# Board_AB_Thumb.net
KiCad netlist of a schematic drawn in Altium Designer
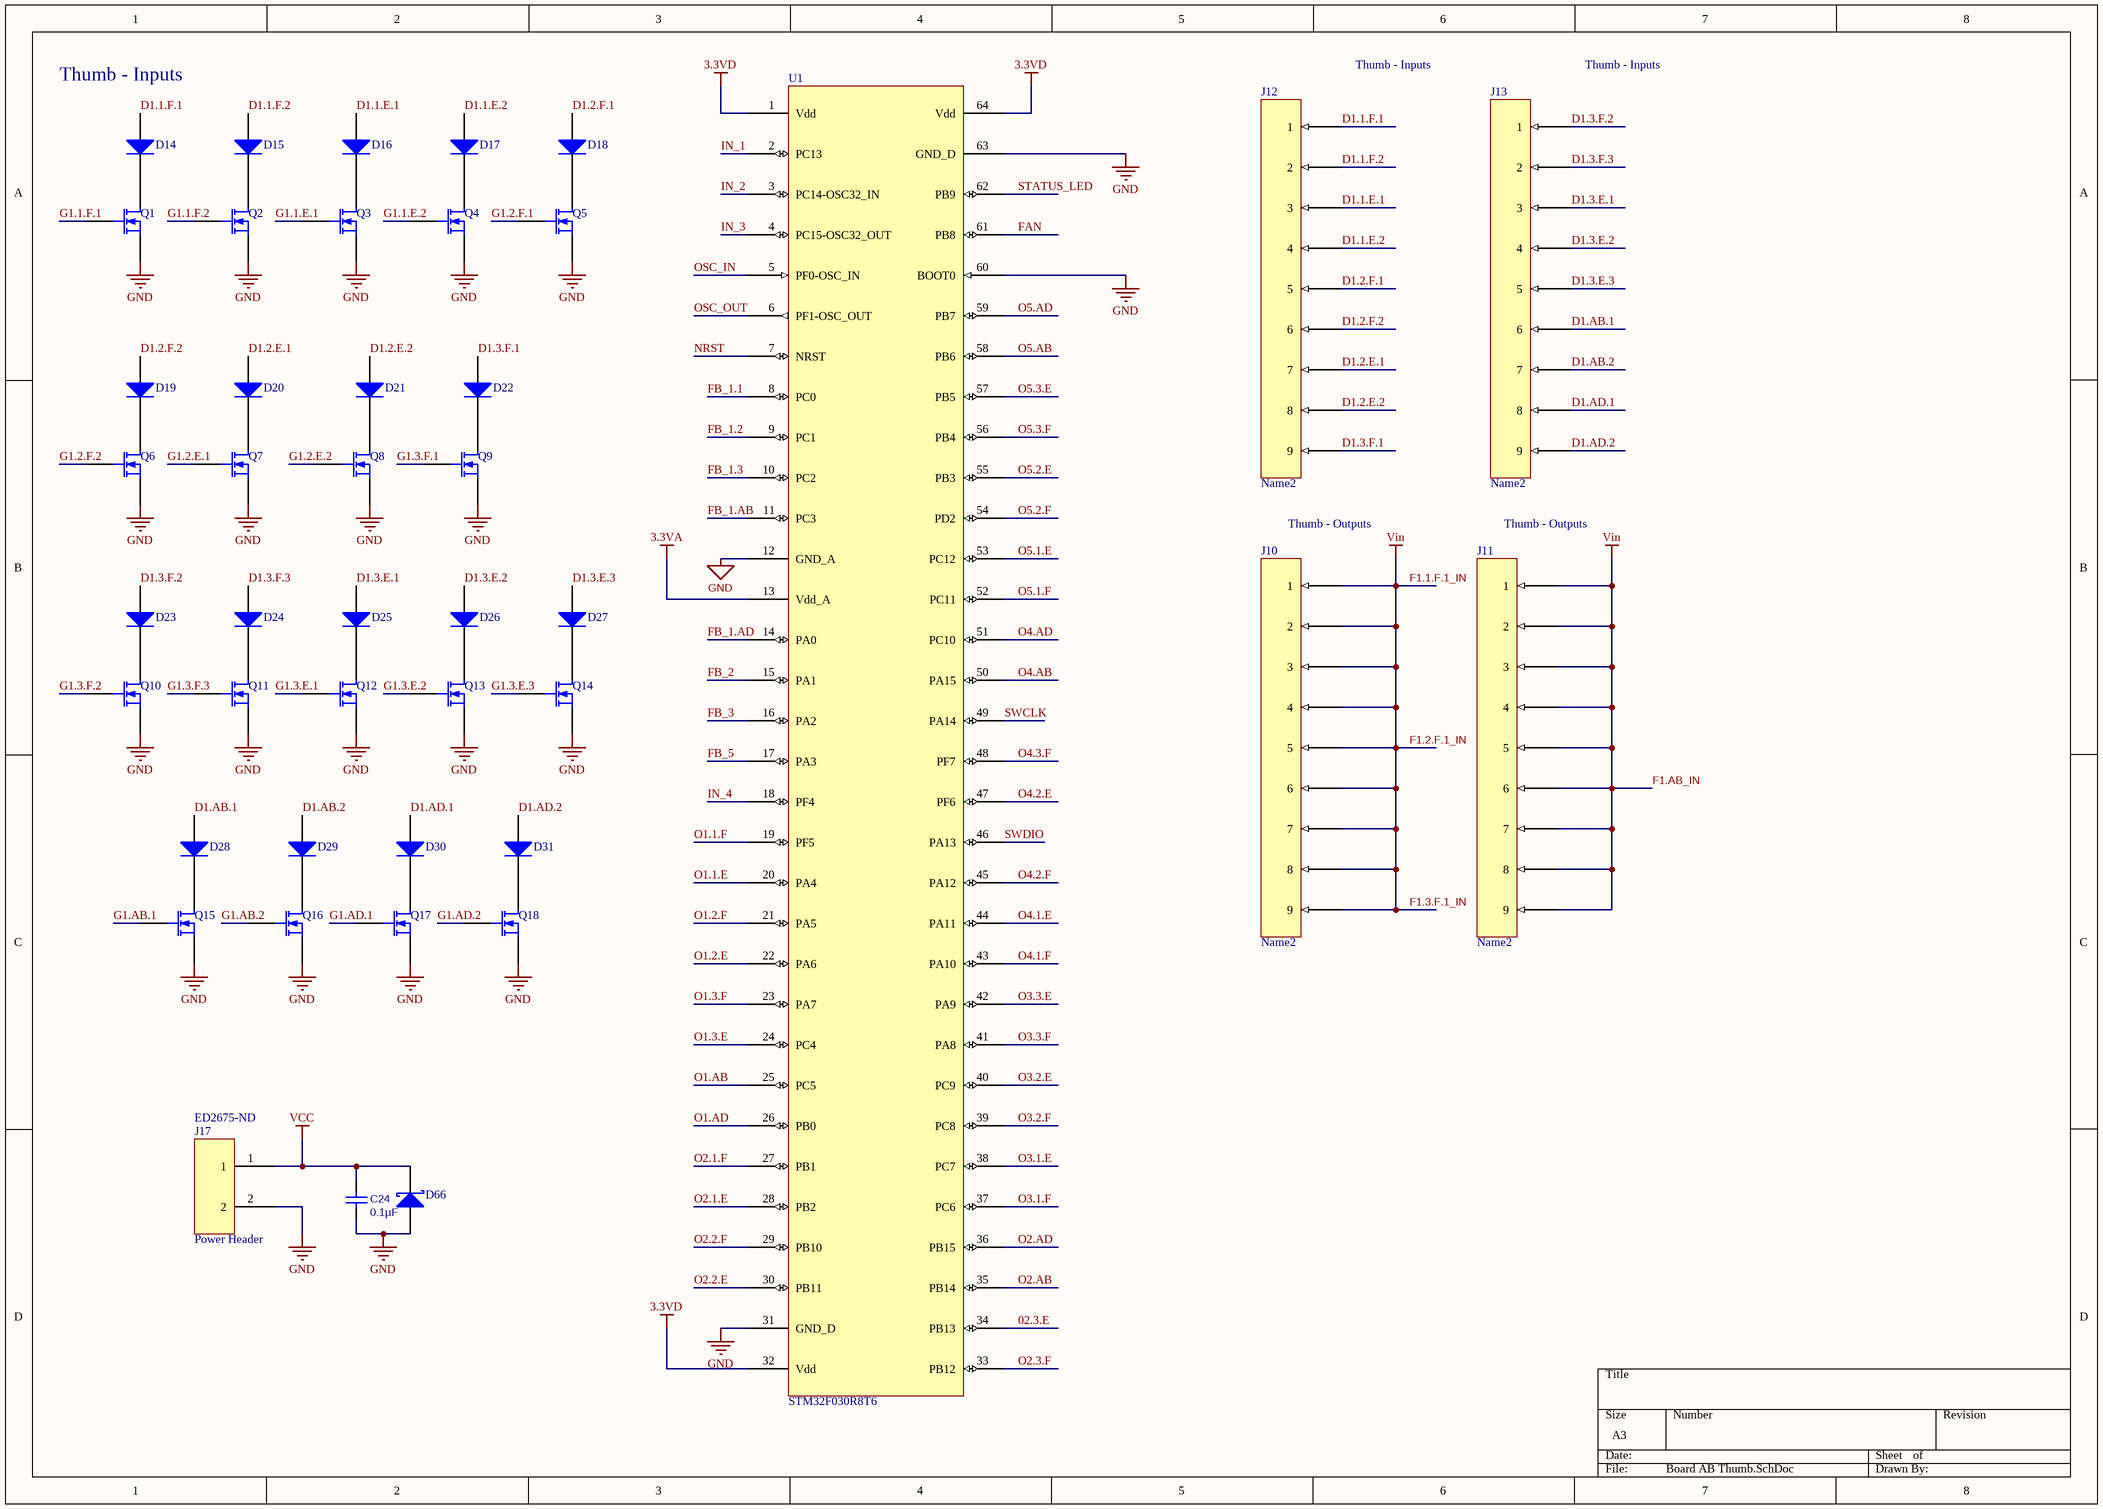
[diagram p0: Board AB Thumb.SchDoc]

(export (version "E")
  (design (tool "Eeschema 10.0.6"))
  (components
    (comp (ref "C24")
      (value "0.1µF")
      (footprint "TDK C-Series (1608)")
      (description "Capacitor")
      (fields (field (name "PUBLISHER") "Altium Limited"))
      (libsource (lib "Miscellaneous Devices") (part "Cap"))
    )
    (comp (ref "D14")
      (value "de")
      (footprint "SMC")
      (description "Default Diode")
      (fields (field (name "PUBLISHER") "Altium Limited"))
      (libsource (lib "Miscellaneous Devices") (part "Diode"))
    )
    (comp (ref "D15")
      (value "de")
      (footprint "SMC")
      (description "Default Diode")
      (fields (field (name "PUBLISHER") "Altium Limited"))
      (libsource (lib "Miscellaneous Devices") (part "Diode"))
    )
    (comp (ref "D16")
      (value "de")
      (footprint "SMC")
      (description "Default Diode")
      (fields (field (name "PUBLISHER") "Altium Limited"))
      (libsource (lib "Miscellaneous Devices") (part "Diode"))
    )
    (comp (ref "D17")
      (value "de")
      (footprint "SMC")
      (description "Default Diode")
      (fields (field (name "PUBLISHER") "Altium Limited"))
      (libsource (lib "Miscellaneous Devices") (part "Diode"))
    )
    (comp (ref "D18")
      (value "de")
      (footprint "SMC")
      (description "Default Diode")
      (fields (field (name "PUBLISHER") "Altium Limited"))
      (libsource (lib "Miscellaneous Devices") (part "Diode"))
    )
    (comp (ref "D19")
      (value "de")
      (footprint "SMC")
      (description "Default Diode")
      (fields (field (name "PUBLISHER") "Altium Limited"))
      (libsource (lib "Miscellaneous Devices") (part "Diode"))
    )
    (comp (ref "D20")
      (value "de")
      (footprint "SMC")
      (description "Default Diode")
      (fields (field (name "PUBLISHER") "Altium Limited"))
      (libsource (lib "Miscellaneous Devices") (part "Diode"))
    )
    (comp (ref "D21")
      (value "de")
      (footprint "SMC")
      (description "Default Diode")
      (fields (field (name "PUBLISHER") "Altium Limited"))
      (libsource (lib "Miscellaneous Devices") (part "Diode"))
    )
    (comp (ref "D22")
      (value "de")
      (footprint "SMC")
      (description "Default Diode")
      (fields (field (name "PUBLISHER") "Altium Limited"))
      (libsource (lib "Miscellaneous Devices") (part "Diode"))
    )
    (comp (ref "D23")
      (value "de")
      (footprint "SMC")
      (description "Default Diode")
      (fields (field (name "PUBLISHER") "Altium Limited"))
      (libsource (lib "Miscellaneous Devices") (part "Diode"))
    )
    (comp (ref "D24")
      (value "de")
      (footprint "SMC")
      (description "Default Diode")
      (fields (field (name "PUBLISHER") "Altium Limited"))
      (libsource (lib "Miscellaneous Devices") (part "Diode"))
    )
    (comp (ref "D25")
      (value "de")
      (footprint "SMC")
      (description "Default Diode")
      (fields (field (name "PUBLISHER") "Altium Limited"))
      (libsource (lib "Miscellaneous Devices") (part "Diode"))
    )
    (comp (ref "D26")
      (value "de")
      (footprint "SMC")
      (description "Default Diode")
      (fields (field (name "PUBLISHER") "Altium Limited"))
      (libsource (lib "Miscellaneous Devices") (part "Diode"))
    )
    (comp (ref "D27")
      (value "de")
      (footprint "SMC")
      (description "Default Diode")
      (fields (field (name "PUBLISHER") "Altium Limited"))
      (libsource (lib "Miscellaneous Devices") (part "Diode"))
    )
    (comp (ref "D28")
      (value "de")
      (footprint "SMC")
      (description "Default Diode")
      (fields (field (name "PUBLISHER") "Altium Limited"))
      (libsource (lib "Miscellaneous Devices") (part "Diode"))
    )
    (comp (ref "D29")
      (value "de")
      (footprint "SMC")
      (description "Default Diode")
      (fields (field (name "PUBLISHER") "Altium Limited"))
      (libsource (lib "Miscellaneous Devices") (part "Diode"))
    )
    (comp (ref "D30")
      (value "de")
      (footprint "SMC")
      (description "Default Diode")
      (fields (field (name "PUBLISHER") "Altium Limited"))
      (libsource (lib "Miscellaneous Devices") (part "Diode"))
    )
    (comp (ref "D31")
      (value "de")
      (footprint "SMC")
      (description "Default Diode")
      (fields (field (name "PUBLISHER") "Altium Limited"))
      (libsource (lib "Miscellaneous Devices") (part "Diode"))
    )
    (comp (ref "D66")
      (value "Diode BAT17")
      (footprint "SOT-23_N")
      (description "Silicon RF Schottky Diode for Mixer Applications in the VHF/UHF Range")
      (fields (field (name "PUBLISHER") "Altium Limited"))
      (libsource (lib "Miscellaneous Devices") (part "Diode BAT17"))
    )
    (comp (ref "J10")
      (value "Name2")
      (description "9 Position header")
      (libsource (lib "Schematics Library") (part "Name2"))
    )
    (comp (ref "J11")
      (value "Name2")
      (description "9 Position header")
      (libsource (lib "Schematics Library") (part "Name2"))
    )
    (comp (ref "J12")
      (value "Name2")
      (description "9 Position header")
      (libsource (lib "Schematics Library") (part "Name2"))
    )
    (comp (ref "J13")
      (value "Name2")
      (description "9 Position header")
      (libsource (lib "Schematics Library") (part "Name2"))
    )
    (comp (ref "J17")
      (value "Power Header")
      (fields (field (name "SUPPLIER PART NUMBER 1") "ED2675-ND"))
      (libsource (lib "Schematics Library") (part "Power Header"))
    )
    (comp (ref "Q1")
      (value "~")
      (description "N-Channel MOSFET")
      (fields (field (name "PUBLISHER") "Altium Limited"))
      (libsource (lib "Miscellaneous Devices") (part "MOSFET-N"))
    )
    (comp (ref "Q2")
      (value "~")
      (description "N-Channel MOSFET")
      (fields (field (name "PUBLISHER") "Altium Limited"))
      (libsource (lib "Miscellaneous Devices") (part "MOSFET-N"))
    )
    (comp (ref "Q3")
      (value "~")
      (description "N-Channel MOSFET")
      (fields (field (name "PUBLISHER") "Altium Limited"))
      (libsource (lib "Miscellaneous Devices") (part "MOSFET-N"))
    )
    (comp (ref "Q4")
      (value "~")
      (description "N-Channel MOSFET")
      (fields (field (name "PUBLISHER") "Altium Limited"))
      (libsource (lib "Miscellaneous Devices") (part "MOSFET-N"))
    )
    (comp (ref "Q5")
      (value "~")
      (description "N-Channel MOSFET")
      (fields (field (name "PUBLISHER") "Altium Limited"))
      (libsource (lib "Miscellaneous Devices") (part "MOSFET-N"))
    )
    (comp (ref "Q6")
      (value "~")
      (description "N-Channel MOSFET")
      (fields (field (name "PUBLISHER") "Altium Limited"))
      (libsource (lib "Miscellaneous Devices") (part "MOSFET-N"))
    )
    (comp (ref "Q7")
      (value "~")
      (description "N-Channel MOSFET")
      (fields (field (name "PUBLISHER") "Altium Limited"))
      (libsource (lib "Miscellaneous Devices") (part "MOSFET-N"))
    )
    (comp (ref "Q8")
      (value "~")
      (description "N-Channel MOSFET")
      (fields (field (name "PUBLISHER") "Altium Limited"))
      (libsource (lib "Miscellaneous Devices") (part "MOSFET-N"))
    )
    (comp (ref "Q9")
      (value "~")
      (description "N-Channel MOSFET")
      (fields (field (name "PUBLISHER") "Altium Limited"))
      (libsource (lib "Miscellaneous Devices") (part "MOSFET-N"))
    )
    (comp (ref "Q10")
      (value "~")
      (description "N-Channel MOSFET")
      (fields (field (name "PUBLISHER") "Altium Limited"))
      (libsource (lib "Miscellaneous Devices") (part "MOSFET-N"))
    )
    (comp (ref "Q11")
      (value "~")
      (description "N-Channel MOSFET")
      (fields (field (name "PUBLISHER") "Altium Limited"))
      (libsource (lib "Miscellaneous Devices") (part "MOSFET-N"))
    )
    (comp (ref "Q12")
      (value "~")
      (description "N-Channel MOSFET")
      (fields (field (name "PUBLISHER") "Altium Limited"))
      (libsource (lib "Miscellaneous Devices") (part "MOSFET-N"))
    )
    (comp (ref "Q13")
      (value "~")
      (description "N-Channel MOSFET")
      (fields (field (name "PUBLISHER") "Altium Limited"))
      (libsource (lib "Miscellaneous Devices") (part "MOSFET-N"))
    )
    (comp (ref "Q14")
      (value "~")
      (description "N-Channel MOSFET")
      (fields (field (name "PUBLISHER") "Altium Limited"))
      (libsource (lib "Miscellaneous Devices") (part "MOSFET-N"))
    )
    (comp (ref "Q15")
      (value "~")
      (description "N-Channel MOSFET")
      (fields (field (name "PUBLISHER") "Altium Limited"))
      (libsource (lib "Miscellaneous Devices") (part "MOSFET-N"))
    )
    (comp (ref "Q16")
      (value "~")
      (description "N-Channel MOSFET")
      (fields (field (name "PUBLISHER") "Altium Limited"))
      (libsource (lib "Miscellaneous Devices") (part "MOSFET-N"))
    )
    (comp (ref "Q17")
      (value "~")
      (description "N-Channel MOSFET")
      (fields (field (name "PUBLISHER") "Altium Limited"))
      (libsource (lib "Miscellaneous Devices") (part "MOSFET-N"))
    )
    (comp (ref "Q18")
      (value "~")
      (description "N-Channel MOSFET")
      (fields (field (name "PUBLISHER") "Altium Limited"))
      (libsource (lib "Miscellaneous Devices") (part "MOSFET-N"))
    )
    (comp (ref "U1") (value "STM32F030R8T6") (libsource (lib "Schematics Library") (part "STM32F030R8T6")))
  )
  (nets
    (net (code "1") (name "/02.3.E") (class "Default")
      (node (ref "U1") (pin "34") (pinfunction "PB13_34") (pintype "bidirectional"))
    )
    (net (code "2") (name "/D1.1.E.1") (class "Default")
      (node (ref "D16") (pin "1") (pinfunction "A_1") (pintype "passive"))
      (node (ref "J12") (pin "3") (pinfunction "3_3") (pintype "input"))
    )
    (net (code "3") (name "/D1.1.E.2") (class "Default")
      (node (ref "D17") (pin "1") (pinfunction "A_1") (pintype "passive"))
      (node (ref "J12") (pin "4") (pinfunction "4_4") (pintype "input"))
    )
    (net (code "4") (name "/D1.1.F.1") (class "Default")
      (node (ref "D14") (pin "1") (pinfunction "A_1") (pintype "passive"))
      (node (ref "J12") (pin "1") (pinfunction "1_1") (pintype "input"))
    )
    (net (code "5") (name "/D1.1.F.2") (class "Default")
      (node (ref "D15") (pin "1") (pinfunction "A_1") (pintype "passive"))
      (node (ref "J12") (pin "66") (pinfunction "2_66") (pintype "input"))
    )
    (net (code "6") (name "/D1.2.E.1") (class "Default")
      (node (ref "D20") (pin "1") (pinfunction "A_1") (pintype "passive"))
      (node (ref "J12") (pin "7") (pinfunction "7_7") (pintype "input"))
    )
    (net (code "7") (name "/D1.2.E.2") (class "Default")
      (node (ref "D21") (pin "1") (pinfunction "A_1") (pintype "passive"))
      (node (ref "J12") (pin "8") (pinfunction "8_8") (pintype "input"))
    )
    (net (code "8") (name "/D1.2.F.1") (class "Default")
      (node (ref "D18") (pin "1") (pinfunction "A_1") (pintype "passive"))
      (node (ref "J12") (pin "5") (pinfunction "5_5") (pintype "input"))
    )
    (net (code "9") (name "/D1.2.F.2") (class "Default")
      (node (ref "D19") (pin "1") (pinfunction "A_1") (pintype "passive"))
      (node (ref "J12") (pin "6") (pinfunction "6_6") (pintype "input"))
    )
    (net (code "10") (name "/D1.3.E.1") (class "Default")
      (node (ref "D25") (pin "1") (pinfunction "A_1") (pintype "passive"))
      (node (ref "J13") (pin "3") (pinfunction "3_3") (pintype "input"))
    )
    (net (code "11") (name "/D1.3.E.2") (class "Default")
      (node (ref "D26") (pin "1") (pinfunction "A_1") (pintype "passive"))
      (node (ref "J13") (pin "4") (pinfunction "4_4") (pintype "input"))
    )
    (net (code "12") (name "/D1.3.E.3") (class "Default")
      (node (ref "D27") (pin "1") (pinfunction "A_1") (pintype "passive"))
      (node (ref "J13") (pin "5") (pinfunction "5_5") (pintype "input"))
    )
    (net (code "13") (name "/D1.3.F.1") (class "Default")
      (node (ref "D22") (pin "1") (pinfunction "A_1") (pintype "passive"))
      (node (ref "J12") (pin "9") (pinfunction "9_9") (pintype "input"))
    )
    (net (code "14") (name "/D1.3.F.2") (class "Default")
      (node (ref "D23") (pin "1") (pinfunction "A_1") (pintype "passive"))
      (node (ref "J13") (pin "1") (pinfunction "1_1") (pintype "input"))
    )
    (net (code "15") (name "/D1.3.F.3") (class "Default")
      (node (ref "D24") (pin "1") (pinfunction "A_1") (pintype "passive"))
      (node (ref "J13") (pin "66") (pinfunction "2_66") (pintype "input"))
    )
    (net (code "16") (name "/D1.AB.1") (class "Default")
      (node (ref "D28") (pin "1") (pinfunction "A_1") (pintype "passive"))
      (node (ref "J13") (pin "6") (pinfunction "6_6") (pintype "input"))
    )
    (net (code "17") (name "/D1.AB.2") (class "Default")
      (node (ref "D29") (pin "1") (pinfunction "A_1") (pintype "passive"))
      (node (ref "J13") (pin "7") (pinfunction "7_7") (pintype "input"))
    )
    (net (code "18") (name "/D1.AD.1") (class "Default")
      (node (ref "D30") (pin "1") (pinfunction "A_1") (pintype "passive"))
      (node (ref "J13") (pin "8") (pinfunction "8_8") (pintype "input"))
    )
    (net (code "19") (name "/D1.AD.2") (class "Default")
      (node (ref "D31") (pin "1") (pinfunction "A_1") (pintype "passive"))
      (node (ref "J13") (pin "9") (pinfunction "9_9") (pintype "input"))
    )
    (net (code "20") (name "/FAN") (class "Default")
      (node (ref "U1") (pin "61") (pinfunction "PB8_61") (pintype "bidirectional"))
    )
    (net (code "21") (name "/FB_1.1") (class "Default")
      (node (ref "U1") (pin "8") (pinfunction "PC0_8") (pintype "bidirectional"))
    )
    (net (code "22") (name "/FB_1.2") (class "Default")
      (node (ref "U1") (pin "9") (pinfunction "PC1_9") (pintype "bidirectional"))
    )
    (net (code "23") (name "/FB_1.3") (class "Default")
      (node (ref "U1") (pin "10") (pinfunction "PC2_10") (pintype "bidirectional"))
    )
    (net (code "24") (name "/FB_1.AB") (class "Default")
      (node (ref "U1") (pin "11") (pinfunction "PC3_11") (pintype "bidirectional"))
    )
    (net (code "25") (name "/FB_1.AD") (class "Default")
      (node (ref "U1") (pin "14") (pinfunction "PA0_14") (pintype "bidirectional"))
    )
    (net (code "26") (name "/FB_2") (class "Default")
      (node (ref "U1") (pin "15") (pinfunction "PA1_15") (pintype "bidirectional"))
    )
    (net (code "27") (name "/FB_3") (class "Default")
      (node (ref "U1") (pin "16") (pinfunction "PA2_16") (pintype "bidirectional"))
    )
    (net (code "28") (name "/FB_5") (class "Default")
      (node (ref "U1") (pin "17") (pinfunction "PA3_17") (pintype "bidirectional"))
    )
    (net (code "29") (name "/G1.1.E.1") (class "Default")
      (node (ref "Q3") (pin "2") (pinfunction "G_2") (pintype "passive"))
    )
    (net (code "30") (name "/G1.1.E.2") (class "Default")
      (node (ref "Q4") (pin "2") (pinfunction "G_2") (pintype "passive"))
    )
    (net (code "31") (name "/G1.1.F.1") (class "Default")
      (node (ref "Q1") (pin "2") (pinfunction "G_2") (pintype "passive"))
    )
    (net (code "32") (name "/G1.1.F.2") (class "Default")
      (node (ref "Q2") (pin "2") (pinfunction "G_2") (pintype "passive"))
    )
    (net (code "33") (name "/G1.2.E.1") (class "Default")
      (node (ref "Q7") (pin "2") (pinfunction "G_2") (pintype "passive"))
    )
    (net (code "34") (name "/G1.2.E.2") (class "Default")
      (node (ref "Q8") (pin "2") (pinfunction "G_2") (pintype "passive"))
    )
    (net (code "35") (name "/G1.2.F.1") (class "Default")
      (node (ref "Q5") (pin "2") (pinfunction "G_2") (pintype "passive"))
    )
    (net (code "36") (name "/G1.2.F.2") (class "Default")
      (node (ref "Q6") (pin "2") (pinfunction "G_2") (pintype "passive"))
    )
    (net (code "37") (name "/G1.3.E.1") (class "Default")
      (node (ref "Q12") (pin "2") (pinfunction "G_2") (pintype "passive"))
    )
    (net (code "38") (name "/G1.3.E.2") (class "Default")
      (node (ref "Q13") (pin "2") (pinfunction "G_2") (pintype "passive"))
    )
    (net (code "39") (name "/G1.3.E.3") (class "Default")
      (node (ref "Q14") (pin "2") (pinfunction "G_2") (pintype "passive"))
    )
    (net (code "40") (name "/G1.3.F.1") (class "Default")
      (node (ref "Q9") (pin "2") (pinfunction "G_2") (pintype "passive"))
    )
    (net (code "41") (name "/G1.3.F.2") (class "Default")
      (node (ref "Q10") (pin "2") (pinfunction "G_2") (pintype "passive"))
    )
    (net (code "42") (name "/G1.3.F.3") (class "Default")
      (node (ref "Q11") (pin "2") (pinfunction "G_2") (pintype "passive"))
    )
    (net (code "43") (name "/G1.AB.1") (class "Default")
      (node (ref "Q15") (pin "2") (pinfunction "G_2") (pintype "passive"))
    )
    (net (code "44") (name "/G1.AB.2") (class "Default")
      (node (ref "Q16") (pin "2") (pinfunction "G_2") (pintype "passive"))
    )
    (net (code "45") (name "/G1.AD.1") (class "Default")
      (node (ref "Q17") (pin "2") (pinfunction "G_2") (pintype "passive"))
    )
    (net (code "46") (name "/G1.AD.2") (class "Default")
      (node (ref "Q18") (pin "2") (pinfunction "G_2") (pintype "passive"))
    )
    (net (code "47") (name "/IN_1") (class "Default")
      (node (ref "U1") (pin "2") (pinfunction "PC13_2") (pintype "bidirectional"))
    )
    (net (code "48") (name "/IN_2") (class "Default")
      (node (ref "U1") (pin "3") (pinfunction "PC14-OSC32_IN_3") (pintype "bidirectional"))
    )
    (net (code "49") (name "/IN_3") (class "Default")
      (node (ref "U1") (pin "4") (pinfunction "PC15-OSC32_OUT_4") (pintype "bidirectional"))
    )
    (net (code "50") (name "/IN_4") (class "Default")
      (node (ref "U1") (pin "18") (pinfunction "PF4_18") (pintype "bidirectional"))
    )
    (net (code "51") (name "/NRST") (class "Default")
      (node (ref "U1") (pin "7") (pinfunction "NRST_7") (pintype "bidirectional"))
    )
    (net (code "52") (name "/O1.1.E") (class "Default")
      (node (ref "U1") (pin "20") (pinfunction "PA4_20") (pintype "bidirectional"))
    )
    (net (code "53") (name "/O1.1.F") (class "Default")
      (node (ref "U1") (pin "19") (pinfunction "PF5_19") (pintype "bidirectional"))
    )
    (net (code "54") (name "/O1.2.E") (class "Default")
      (node (ref "U1") (pin "22") (pinfunction "PA6_22") (pintype "bidirectional"))
    )
    (net (code "55") (name "/O1.2.F") (class "Default")
      (node (ref "U1") (pin "21") (pinfunction "PA5_21") (pintype "bidirectional"))
    )
    (net (code "56") (name "/O1.3.E") (class "Default")
      (node (ref "U1") (pin "24") (pinfunction "PC4_24") (pintype "bidirectional"))
    )
    (net (code "57") (name "/O1.3.F") (class "Default")
      (node (ref "U1") (pin "23") (pinfunction "PA7_23") (pintype "bidirectional"))
    )
    (net (code "58") (name "/O1.AB") (class "Default")
      (node (ref "U1") (pin "25") (pinfunction "PC5_25") (pintype "bidirectional"))
    )
    (net (code "59") (name "/O1.AD") (class "Default")
      (node (ref "U1") (pin "26") (pinfunction "PB0_26") (pintype "bidirectional"))
    )
    (net (code "60") (name "/O2.1.E") (class "Default")
      (node (ref "U1") (pin "28") (pinfunction "PB2_28") (pintype "bidirectional"))
    )
    (net (code "61") (name "/O2.1.F") (class "Default")
      (node (ref "U1") (pin "27") (pinfunction "PB1_27") (pintype "bidirectional"))
    )
    (net (code "62") (name "/O2.2.E") (class "Default")
      (node (ref "U1") (pin "30") (pinfunction "PB11_30") (pintype "bidirectional"))
    )
    (net (code "63") (name "/O2.2.F") (class "Default")
      (node (ref "U1") (pin "29") (pinfunction "PB10_29") (pintype "bidirectional"))
    )
    (net (code "64") (name "/O2.3.F") (class "Default")
      (node (ref "U1") (pin "33") (pinfunction "PB12_33") (pintype "bidirectional"))
    )
    (net (code "65") (name "/O2.AB") (class "Default")
      (node (ref "U1") (pin "35") (pinfunction "PB14_35") (pintype "bidirectional"))
    )
    (net (code "66") (name "/O2.AD") (class "Default")
      (node (ref "U1") (pin "36") (pinfunction "PB15_36") (pintype "bidirectional"))
    )
    (net (code "67") (name "/O3.1.E") (class "Default")
      (node (ref "U1") (pin "38") (pinfunction "PC7_38") (pintype "bidirectional"))
    )
    (net (code "68") (name "/O3.1.F") (class "Default")
      (node (ref "U1") (pin "37") (pinfunction "PC6_37") (pintype "bidirectional"))
    )
    (net (code "69") (name "/O3.2.E") (class "Default")
      (node (ref "U1") (pin "40") (pinfunction "PC9_40") (pintype "bidirectional"))
    )
    (net (code "70") (name "/O3.2.F") (class "Default")
      (node (ref "U1") (pin "39") (pinfunction "PC8_39") (pintype "bidirectional"))
    )
    (net (code "71") (name "/O3.3.E") (class "Default")
      (node (ref "U1") (pin "42") (pinfunction "PA9_42") (pintype "bidirectional"))
    )
    (net (code "72") (name "/O3.3.F") (class "Default")
      (node (ref "U1") (pin "41") (pinfunction "PA8_41") (pintype "bidirectional"))
    )
    (net (code "73") (name "/O4.1.E") (class "Default")
      (node (ref "U1") (pin "44") (pinfunction "PA11_44") (pintype "bidirectional"))
    )
    (net (code "74") (name "/O4.1.F") (class "Default")
      (node (ref "U1") (pin "43") (pinfunction "PA10_43") (pintype "bidirectional"))
    )
    (net (code "75") (name "/O4.2.E") (class "Default")
      (node (ref "U1") (pin "47") (pinfunction "PF6_47") (pintype "bidirectional"))
    )
    (net (code "76") (name "/O4.2.F") (class "Default")
      (node (ref "U1") (pin "45") (pinfunction "PA12_45") (pintype "bidirectional"))
    )
    (net (code "77") (name "/O4.3.F") (class "Default")
      (node (ref "U1") (pin "48") (pinfunction "PF7_48") (pintype "bidirectional"))
    )
    (net (code "78") (name "/O4.AB") (class "Default")
      (node (ref "U1") (pin "50") (pinfunction "PA15_50") (pintype "bidirectional"))
    )
    (net (code "79") (name "/O4.AD") (class "Default")
      (node (ref "U1") (pin "51") (pinfunction "PC10_51") (pintype "bidirectional"))
    )
    (net (code "80") (name "/O5.1.E") (class "Default")
      (node (ref "U1") (pin "53") (pinfunction "PC12_53") (pintype "bidirectional"))
    )
    (net (code "81") (name "/O5.1.F") (class "Default")
      (node (ref "U1") (pin "52") (pinfunction "PC11_52") (pintype "bidirectional"))
    )
    (net (code "82") (name "/O5.2.E") (class "Default")
      (node (ref "U1") (pin "55") (pinfunction "PB3_55") (pintype "bidirectional"))
    )
    (net (code "83") (name "/O5.2.F") (class "Default")
      (node (ref "U1") (pin "54") (pinfunction "PD2_54") (pintype "bidirectional"))
    )
    (net (code "84") (name "/O5.3.E") (class "Default")
      (node (ref "U1") (pin "57") (pinfunction "PB5_57") (pintype "bidirectional"))
    )
    (net (code "85") (name "/O5.3.F") (class "Default")
      (node (ref "U1") (pin "56") (pinfunction "PB4_56") (pintype "bidirectional"))
    )
    (net (code "86") (name "/O5.AB") (class "Default")
      (node (ref "U1") (pin "58") (pinfunction "PB6_58") (pintype "bidirectional"))
    )
    (net (code "87") (name "/O5.AD") (class "Default")
      (node (ref "U1") (pin "59") (pinfunction "PB7_59") (pintype "bidirectional"))
    )
    (net (code "88") (name "/OSC_IN") (class "Default")
      (node (ref "U1") (pin "5") (pinfunction "PF0-OSC_IN_5") (pintype "input"))
    )
    (net (code "89") (name "/OSC_OUT") (class "Default")
      (node (ref "U1") (pin "6") (pinfunction "PF1-OSC_OUT_6") (pintype "output"))
    )
    (net (code "90") (name "/STATUS_LED") (class "Default")
      (node (ref "U1") (pin "62") (pinfunction "PB9_62") (pintype "bidirectional"))
    )
    (net (code "91") (name "/SWCLK") (class "Default")
      (node (ref "U1") (pin "49") (pinfunction "PA14_49") (pintype "bidirectional"))
    )
    (net (code "92") (name "/SWDIO") (class "Default")
      (node (ref "U1") (pin "46") (pinfunction "PA13_46") (pintype "bidirectional"))
    )
    (net (code "93") (name "3.3VA") (class "Default")
      (node (ref "U1") (pin "13") (pinfunction "Vdd_A_13") (pintype "power_in"))
    )
    (net (code "94") (name "3.3VD") (class "Default")
      (node (ref "U1") (pin "1") (pinfunction "Vdd_1") (pintype "power_in"))
      (node (ref "U1") (pin "32") (pinfunction "Vdd_32") (pintype "power_in"))
      (node (ref "U1") (pin "64") (pinfunction "Vdd_64") (pintype "power_in"))
    )
    (net (code "95") (name "GND") (class "Default")
      (node (ref "C24") (pin "1") (pinfunction "1_1") (pintype "passive"))
      (node (ref "D66") (pin "1") (pinfunction "A_1") (pintype "passive"))
      (node (ref "J17") (pin "2") (pinfunction "2_2") (pintype "power_in"))
      (node (ref "Q1") (pin "3") (pinfunction "S_3") (pintype "passive"))
      (node (ref "Q10") (pin "3") (pinfunction "S_3") (pintype "passive"))
      (node (ref "Q11") (pin "3") (pinfunction "S_3") (pintype "passive"))
      (node (ref "Q12") (pin "3") (pinfunction "S_3") (pintype "passive"))
      (node (ref "Q13") (pin "3") (pinfunction "S_3") (pintype "passive"))
      (node (ref "Q14") (pin "3") (pinfunction "S_3") (pintype "passive"))
      (node (ref "Q15") (pin "3") (pinfunction "S_3") (pintype "passive"))
      (node (ref "Q16") (pin "3") (pinfunction "S_3") (pintype "passive"))
      (node (ref "Q17") (pin "3") (pinfunction "S_3") (pintype "passive"))
      (node (ref "Q18") (pin "3") (pinfunction "S_3") (pintype "passive"))
      (node (ref "Q2") (pin "3") (pinfunction "S_3") (pintype "passive"))
      (node (ref "Q3") (pin "3") (pinfunction "S_3") (pintype "passive"))
      (node (ref "Q4") (pin "3") (pinfunction "S_3") (pintype "passive"))
      (node (ref "Q5") (pin "3") (pinfunction "S_3") (pintype "passive"))
      (node (ref "Q6") (pin "3") (pinfunction "S_3") (pintype "passive"))
      (node (ref "Q7") (pin "3") (pinfunction "S_3") (pintype "passive"))
      (node (ref "Q8") (pin "3") (pinfunction "S_3") (pintype "passive"))
      (node (ref "Q9") (pin "3") (pinfunction "S_3") (pintype "passive"))
      (node (ref "U1") (pin "12") (pinfunction "GND_A_12") (pintype "power_in"))
      (node (ref "U1") (pin "31") (pinfunction "GND_D_31") (pintype "power_in"))
      (node (ref "U1") (pin "60") (pinfunction "BOOT0_60") (pintype "input"))
      (node (ref "U1") (pin "63") (pinfunction "GND_D_63") (pintype "passive"))
    )
    (net (code "96") (name "Net-(D14-K)") (class "Default")
      (node (ref "D14") (pin "2") (pinfunction "K_2") (pintype "passive"))
      (node (ref "Q1") (pin "1") (pinfunction "D_1") (pintype "passive"))
    )
    (net (code "97") (name "Net-(D15-K)") (class "Default")
      (node (ref "D15") (pin "2") (pinfunction "K_2") (pintype "passive"))
      (node (ref "Q2") (pin "1") (pinfunction "D_1") (pintype "passive"))
    )
    (net (code "98") (name "Net-(D16-K)") (class "Default")
      (node (ref "D16") (pin "2") (pinfunction "K_2") (pintype "passive"))
      (node (ref "Q3") (pin "1") (pinfunction "D_1") (pintype "passive"))
    )
    (net (code "99") (name "Net-(D17-K)") (class "Default")
      (node (ref "D17") (pin "2") (pinfunction "K_2") (pintype "passive"))
      (node (ref "Q4") (pin "1") (pinfunction "D_1") (pintype "passive"))
    )
    (net (code "100") (name "Net-(D18-K)") (class "Default")
      (node (ref "D18") (pin "2") (pinfunction "K_2") (pintype "passive"))
      (node (ref "Q5") (pin "1") (pinfunction "D_1") (pintype "passive"))
    )
    (net (code "101") (name "Net-(D19-K)") (class "Default")
      (node (ref "D19") (pin "2") (pinfunction "K_2") (pintype "passive"))
      (node (ref "Q6") (pin "1") (pinfunction "D_1") (pintype "passive"))
    )
    (net (code "102") (name "Net-(D20-K)") (class "Default")
      (node (ref "D20") (pin "2") (pinfunction "K_2") (pintype "passive"))
      (node (ref "Q7") (pin "1") (pinfunction "D_1") (pintype "passive"))
    )
    (net (code "103") (name "Net-(D21-K)") (class "Default")
      (node (ref "D21") (pin "2") (pinfunction "K_2") (pintype "passive"))
      (node (ref "Q8") (pin "1") (pinfunction "D_1") (pintype "passive"))
    )
    (net (code "104") (name "Net-(D22-K)") (class "Default")
      (node (ref "D22") (pin "2") (pinfunction "K_2") (pintype "passive"))
      (node (ref "Q9") (pin "1") (pinfunction "D_1") (pintype "passive"))
    )
    (net (code "105") (name "Net-(D23-K)") (class "Default")
      (node (ref "D23") (pin "2") (pinfunction "K_2") (pintype "passive"))
      (node (ref "Q10") (pin "1") (pinfunction "D_1") (pintype "passive"))
    )
    (net (code "106") (name "Net-(D24-K)") (class "Default")
      (node (ref "D24") (pin "2") (pinfunction "K_2") (pintype "passive"))
      (node (ref "Q11") (pin "1") (pinfunction "D_1") (pintype "passive"))
    )
    (net (code "107") (name "Net-(D25-K)") (class "Default")
      (node (ref "D25") (pin "2") (pinfunction "K_2") (pintype "passive"))
      (node (ref "Q12") (pin "1") (pinfunction "D_1") (pintype "passive"))
    )
    (net (code "108") (name "Net-(D26-K)") (class "Default")
      (node (ref "D26") (pin "2") (pinfunction "K_2") (pintype "passive"))
      (node (ref "Q13") (pin "1") (pinfunction "D_1") (pintype "passive"))
    )
    (net (code "109") (name "Net-(D27-K)") (class "Default")
      (node (ref "D27") (pin "2") (pinfunction "K_2") (pintype "passive"))
      (node (ref "Q14") (pin "1") (pinfunction "D_1") (pintype "passive"))
    )
    (net (code "110") (name "Net-(D28-K)") (class "Default")
      (node (ref "D28") (pin "2") (pinfunction "K_2") (pintype "passive"))
      (node (ref "Q15") (pin "1") (pinfunction "D_1") (pintype "passive"))
    )
    (net (code "111") (name "Net-(D29-K)") (class "Default")
      (node (ref "D29") (pin "2") (pinfunction "K_2") (pintype "passive"))
      (node (ref "Q16") (pin "1") (pinfunction "D_1") (pintype "passive"))
    )
    (net (code "112") (name "Net-(D30-K)") (class "Default")
      (node (ref "D30") (pin "2") (pinfunction "K_2") (pintype "passive"))
      (node (ref "Q17") (pin "1") (pinfunction "D_1") (pintype "passive"))
    )
    (net (code "113") (name "Net-(D31-K)") (class "Default")
      (node (ref "D31") (pin "2") (pinfunction "K_2") (pintype "passive"))
      (node (ref "Q18") (pin "1") (pinfunction "D_1") (pintype "passive"))
    )
    (net (code "114") (name "VCC") (class "Default")
      (node (ref "C24") (pin "2") (pinfunction "2_2") (pintype "passive"))
      (node (ref "D66") (pin "3") (pinfunction "K_3") (pintype "passive"))
      (node (ref "J17") (pin "1") (pinfunction "1_1") (pintype "power_in"))
    )
    (net (code "115") (name "Vin") (class "Default")
      (node (ref "J10") (pin "1") (pinfunction "1_1") (pintype "input"))
      (node (ref "J10") (pin "3") (pinfunction "3_3") (pintype "input"))
      (node (ref "J10") (pin "4") (pinfunction "4_4") (pintype "input"))
      (node (ref "J10") (pin "5") (pinfunction "5_5") (pintype "input"))
      (node (ref "J10") (pin "6") (pinfunction "6_6") (pintype "input"))
      (node (ref "J10") (pin "66") (pinfunction "2_66") (pintype "input"))
      (node (ref "J10") (pin "7") (pinfunction "7_7") (pintype "input"))
      (node (ref "J10") (pin "8") (pinfunction "8_8") (pintype "input"))
      (node (ref "J10") (pin "9") (pinfunction "9_9") (pintype "input"))
      (node (ref "J11") (pin "1") (pinfunction "1_1") (pintype "input"))
      (node (ref "J11") (pin "3") (pinfunction "3_3") (pintype "input"))
      (node (ref "J11") (pin "4") (pinfunction "4_4") (pintype "input"))
      (node (ref "J11") (pin "5") (pinfunction "5_5") (pintype "input"))
      (node (ref "J11") (pin "6") (pinfunction "6_6") (pintype "input"))
      (node (ref "J11") (pin "66") (pinfunction "2_66") (pintype "input"))
      (node (ref "J11") (pin "7") (pinfunction "7_7") (pintype "input"))
      (node (ref "J11") (pin "8") (pinfunction "8_8") (pintype "input"))
      (node (ref "J11") (pin "9") (pinfunction "9_9") (pintype "input"))
    )
  )
)
